# SCH_SYNTH_2024-10-22.net
KiCad netlist of a schematic drawn in EasyEDA
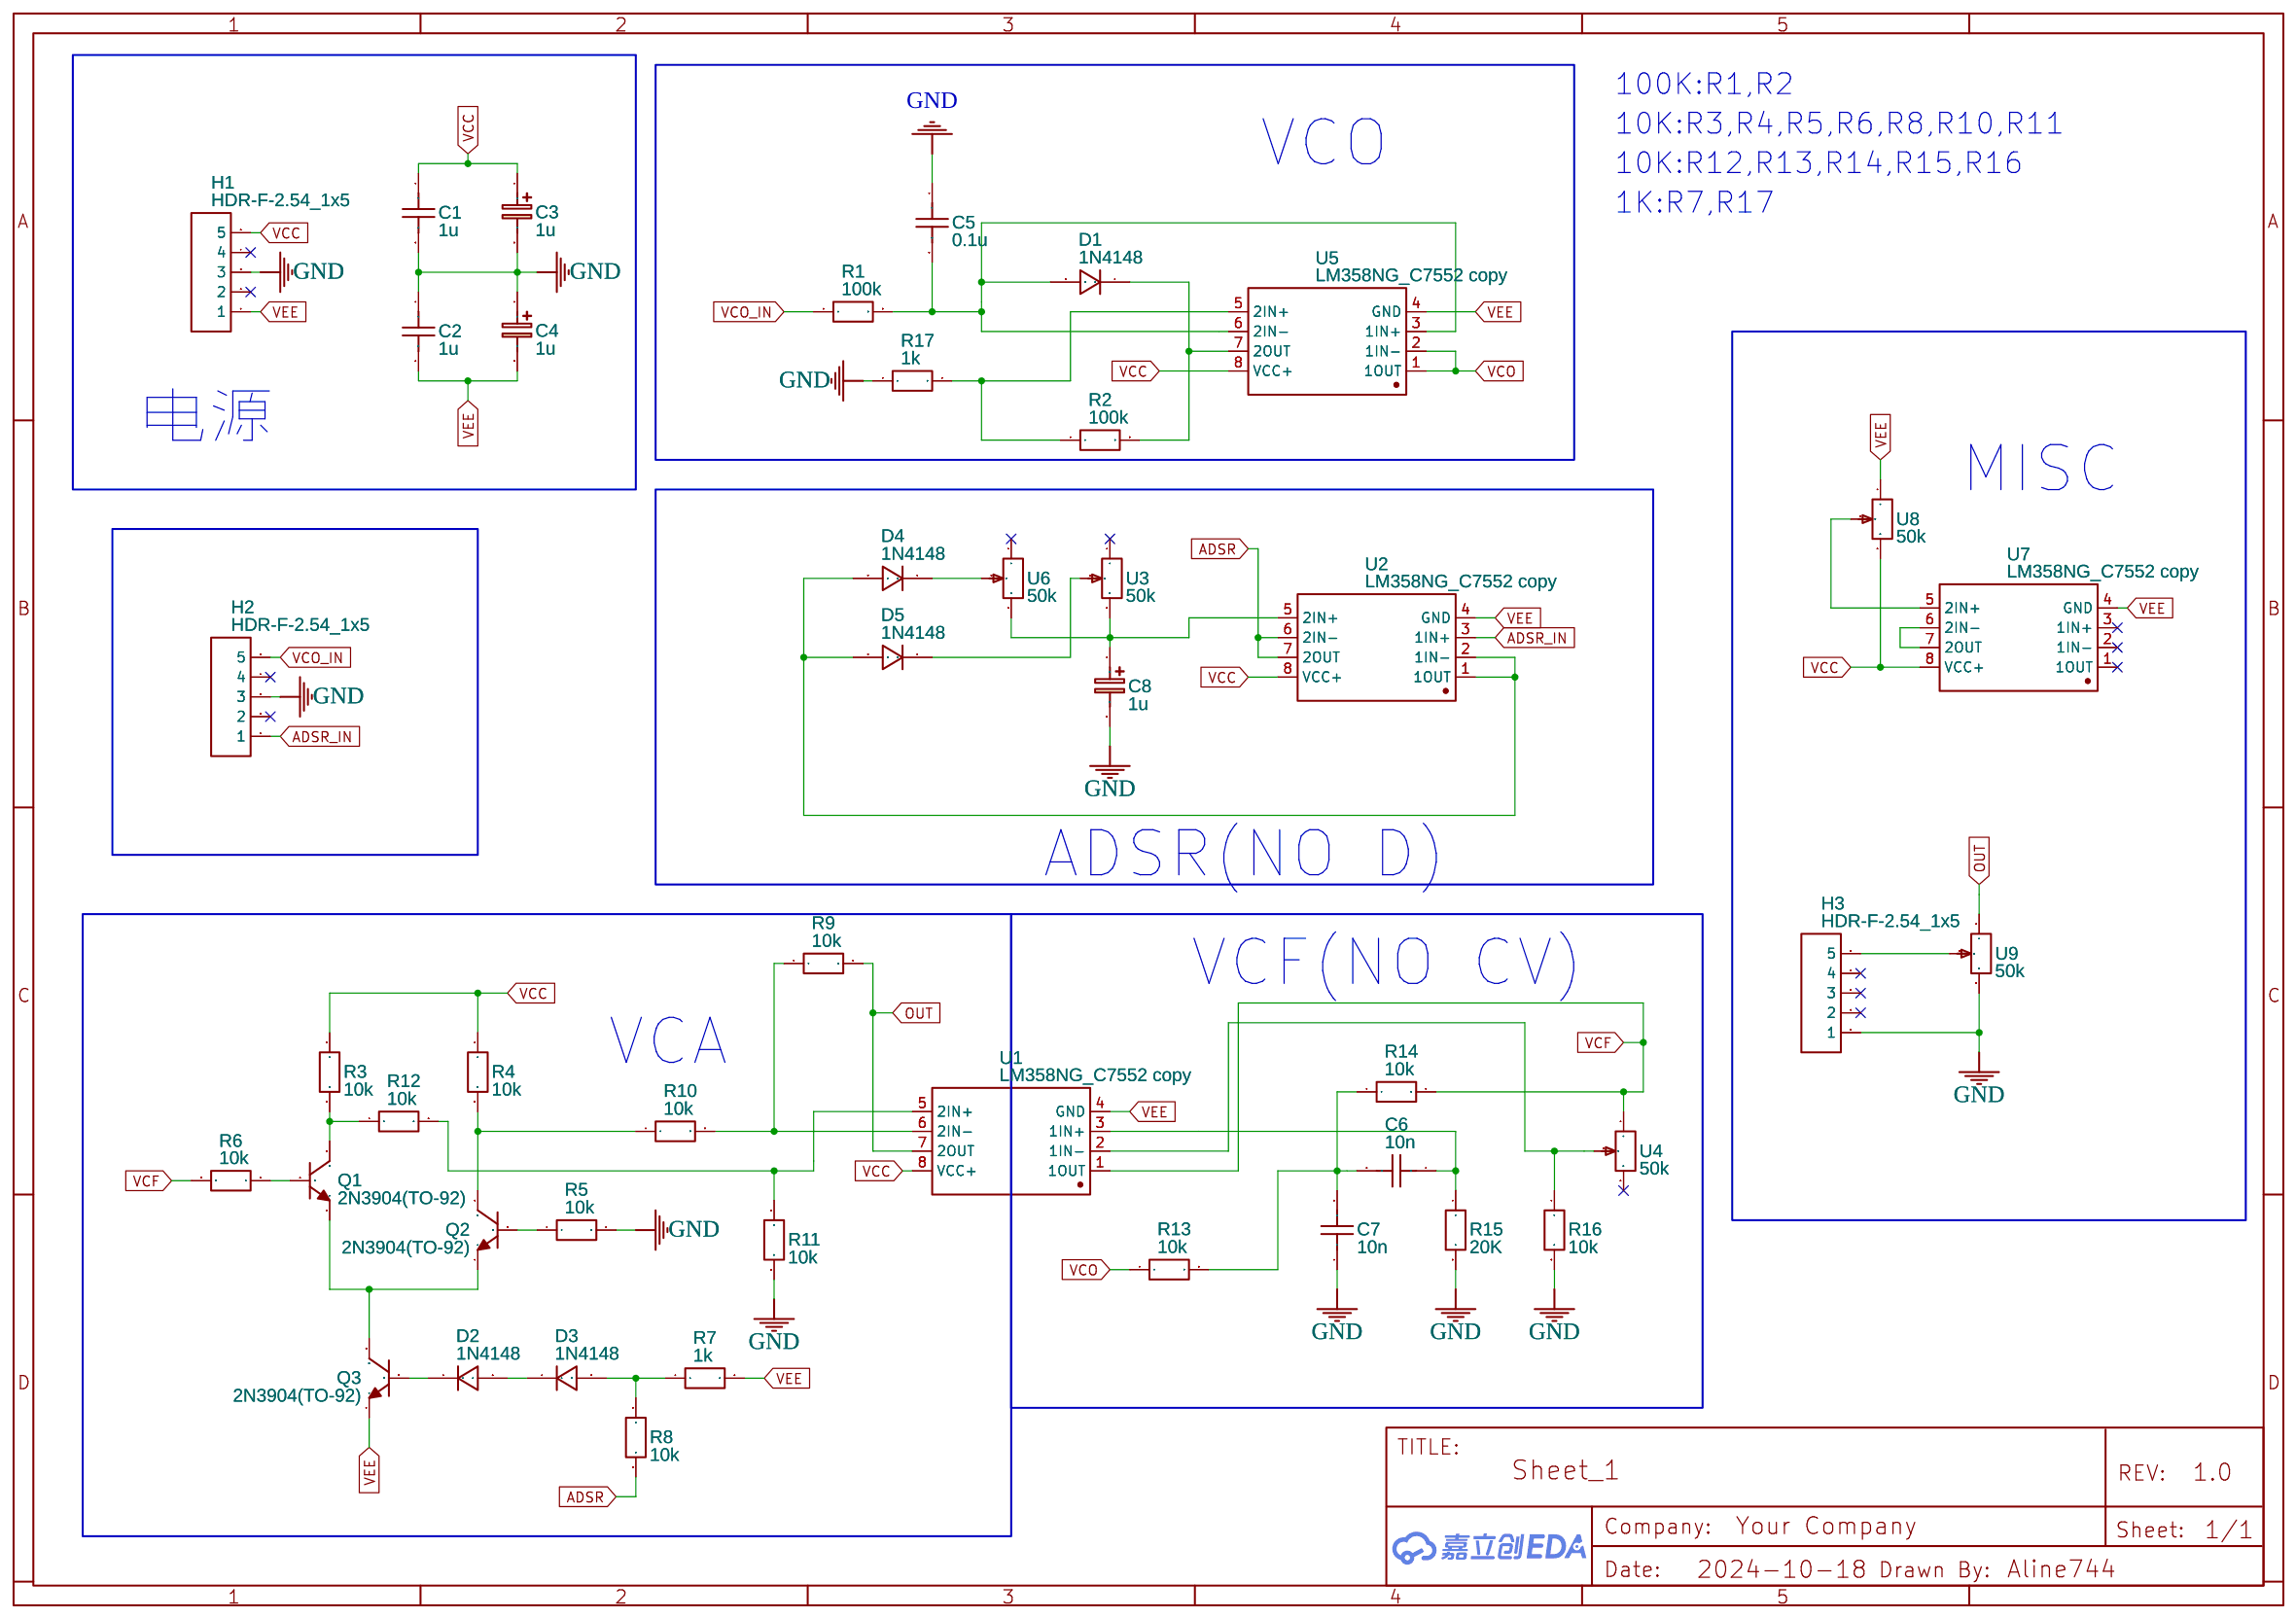
[diagram p0: schematic sheet]

(export (version "E")
  (design (tool "Eeschema 10.0.6"))
  (components
    (comp (ref "C1") (value "1u") (libsource (lib "") (part "C_RAD-0.2_US")))
    (comp (ref "C2") (value "1u") (libsource (lib "") (part "C_RAD-0.2_US")))
    (comp (ref "C3") (value "1u") (libsource (lib "") (part "CE_TH_D8.0×F3.5_EU_1")))
    (comp (ref "C4") (value "1u") (libsource (lib "") (part "CE_TH_D8.0×F3.5_EU_1")))
    (comp (ref "C5") (value "0.1u") (libsource (lib "") (part "C_RAD-0.2_US")))
    (comp (ref "C6") (value "10n") (libsource (lib "") (part "C_RAD-0.2_US_1")))
    (comp (ref "C7") (value "10n") (libsource (lib "") (part "C_RAD-0.2_US_2")))
    (comp (ref "C8") (value "1u") (libsource (lib "") (part "CE_TH_D8.0×F3.5_EU")))
    (comp (ref "D1")
      (value "1N4148")
      (fields (field (name "BOM_Supplier Part") "C13769"))
      (libsource (lib "") (part "1N4148"))
    )
    (comp (ref "D2")
      (value "1N4148")
      (fields (field (name "BOM_Supplier Part") "C13769"))
      (libsource (lib "") (part "1N4148_1"))
    )
    (comp (ref "D3")
      (value "1N4148")
      (fields (field (name "BOM_Supplier Part") "C13769"))
      (libsource (lib "") (part "1N4148_1"))
    )
    (comp (ref "D4")
      (value "1N4148")
      (fields (field (name "BOM_Supplier Part") "C13769"))
      (libsource (lib "") (part "1N4148"))
    )
    (comp (ref "D5")
      (value "1N4148")
      (fields (field (name "BOM_Supplier Part") "C13769"))
      (libsource (lib "") (part "1N4148"))
    )
    (comp (ref "H1")
      (value "HDR-F-2.54_1x5")
      (fields (field (name "BOM_Supplier Part") "C50950"))
      (libsource (lib "") (part "HDR-F-2.54_1x5"))
    )
    (comp (ref "H2")
      (value "HDR-F-2.54_1x5")
      (fields (field (name "BOM_Supplier Part") "C50950"))
      (libsource (lib "") (part "HDR-F-2.54_1x5"))
    )
    (comp (ref "H3")
      (value "HDR-F-2.54_1x5")
      (fields (field (name "BOM_Supplier Part") "C50950"))
      (libsource (lib "") (part "HDR-F-2.54_1x5"))
    )
    (comp (ref "Q1")
      (value "2N3904(TO-92)")
      (fields (field (name "BOM_Manufacturer Part") "2N3904") (field (name "BOM_Supplier Part") "C118538"))
      (libsource (lib "") (part "2N3904(TO-92)"))
    )
    (comp (ref "Q2")
      (value "2N3904(TO-92)")
      (fields (field (name "BOM_Manufacturer Part") "2N3904") (field (name "BOM_Supplier Part") "C118538"))
      (libsource (lib "") (part "2N3904(TO-92)_1"))
    )
    (comp (ref "Q3")
      (value "2N3904(TO-92)")
      (fields (field (name "BOM_Manufacturer Part") "2N3904") (field (name "BOM_Supplier Part") "C118538"))
      (libsource (lib "") (part "2N3904(TO-92)_1"))
    )
    (comp (ref "R1") (value "100k") (libsource (lib "") (part "R_AXIAL-0.3_EU_1")))
    (comp (ref "R2") (value "100k") (libsource (lib "") (part "R_AXIAL-0.3_EU_1")))
    (comp (ref "R3") (value "10k") (libsource (lib "") (part "R_AXIAL-0.3_EU")))
    (comp (ref "R4") (value "10k") (libsource (lib "") (part "R_AXIAL-0.3_EU")))
    (comp (ref "R5") (value "10k") (libsource (lib "") (part "R_AXIAL-0.3_EU_1")))
    (comp (ref "R6") (value "10k") (libsource (lib "") (part "R_AXIAL-0.3_EU_2")))
    (comp (ref "R7") (value "1k") (libsource (lib "") (part "R_AXIAL-0.3_EU_1")))
    (comp (ref "R8") (value "10k") (libsource (lib "") (part "R_AXIAL-0.3_EU")))
    (comp (ref "R9") (value "10k") (libsource (lib "") (part "R_AXIAL-0.3_EU_1")))
    (comp (ref "R10") (value "10k") (libsource (lib "") (part "R_AXIAL-0.3_EU_1")))
    (comp (ref "R11") (value "10k") (libsource (lib "") (part "R_AXIAL-0.3_EU")))
    (comp (ref "R12") (value "10k") (libsource (lib "") (part "R_AXIAL-0.3_EU_1")))
    (comp (ref "R13") (value "10k") (libsource (lib "") (part "R_AXIAL-0.3_EU_1")))
    (comp (ref "R14") (value "10k") (libsource (lib "") (part "R_AXIAL-0.3_EU_1")))
    (comp (ref "R15") (value "20K") (libsource (lib "") (part "R_AXIAL-0.3_EU")))
    (comp (ref "R16") (value "10k") (libsource (lib "") (part "R_AXIAL-0.3_EU")))
    (comp (ref "R17") (value "1k") (libsource (lib "") (part "R_AXIAL-0.3_EU_1")))
    (comp (ref "U1")
      (value "LM358NG_C7552 copy")
      (fields (field (name "Manufacturer Part") "LM358NG") (field (name "Manufacturer") "ON"))
      (libsource (lib "") (part "LM358NG_C7552 copy"))
    )
    (comp (ref "U2")
      (value "LM358NG_C7552 copy")
      (fields (field (name "Manufacturer Part") "LM358NG") (field (name "Manufacturer") "ON"))
      (libsource (lib "") (part "LM358NG_C7552 copy"))
    )
    (comp (ref "U3") (value "50k") (libsource (lib "") (part "蓝白可调电阻")))
    (comp (ref "U4") (value "50k") (libsource (lib "") (part "蓝白可调电阻")))
    (comp (ref "U5")
      (value "LM358NG_C7552 copy")
      (fields (field (name "Manufacturer Part") "LM358NG") (field (name "Manufacturer") "ON"))
      (libsource (lib "") (part "LM358NG_C7552 copy"))
    )
    (comp (ref "U6") (value "50k") (libsource (lib "") (part "蓝白可调电阻")))
    (comp (ref "U7")
      (value "LM358NG_C7552 copy")
      (fields (field (name "Manufacturer Part") "LM358NG") (field (name "Manufacturer") "ON"))
      (libsource (lib "") (part "LM358NG_C7552 copy"))
    )
    (comp (ref "U8") (value "50k") (libsource (lib "") (part "蓝白可调电阻")))
    (comp (ref "U9") (value "50k") (libsource (lib "") (part "蓝白可调电阻")))
  )
  (nets
    (net (code "1") (name "ADSR") (class "Default")
      (node (ref "R8") (pin "2") (pinfunction "2_2") (pintype "unspecified"))
      (node (ref "U2") (pin "6") (pinfunction "2IN-_6") (pintype "unspecified"))
      (node (ref "U2") (pin "7") (pinfunction "2OUT_7") (pintype "unspecified"))
    )
    (net (code "2") (name "ADSR_IN") (class "Default")
      (node (ref "H2") (pin "1") (pinfunction "1_1") (pintype "unspecified"))
      (node (ref "U2") (pin "3") (pinfunction "1IN+_3") (pintype "unspecified"))
    )
    (net (code "3") (name "GND") (class "Default")
      (node (ref "C1") (pin "2") (pinfunction "2_2") (pintype "unspecified"))
      (node (ref "C2") (pin "1") (pinfunction "1_1") (pintype "unspecified"))
      (node (ref "C3") (pin "2") (pinfunction "2_2") (pintype "unspecified"))
      (node (ref "C4") (pin "1") (pinfunction "1_1") (pintype "unspecified"))
      (node (ref "C5") (pin "1") (pinfunction "1_1") (pintype "unspecified"))
      (node (ref "C7") (pin "1") (pinfunction "1_1") (pintype "unspecified"))
      (node (ref "C8") (pin "2") (pinfunction "2_2") (pintype "unspecified"))
      (node (ref "H1") (pin "3") (pinfunction "3_3") (pintype "unspecified"))
      (node (ref "H2") (pin "3") (pinfunction "3_3") (pintype "unspecified"))
      (node (ref "H3") (pin "1") (pinfunction "1_1") (pintype "unspecified"))
      (node (ref "R11") (pin "2") (pinfunction "2_2") (pintype "unspecified"))
      (node (ref "R15") (pin "2") (pinfunction "2_2") (pintype "unspecified"))
      (node (ref "R16") (pin "2") (pinfunction "2_2") (pintype "unspecified"))
      (node (ref "R17") (pin "1") (pinfunction "1_1") (pintype "unspecified"))
      (node (ref "R5") (pin "2") (pinfunction "2_2") (pintype "unspecified"))
      (node (ref "U9") (pin "2") (pinfunction "2_2") (pintype "input"))
    )
    (net (code "4") (name "Net-(C6-Pad2)") (class "Default")
      (node (ref "C6") (pin "2") (pinfunction "2_2") (pintype "unspecified"))
      (node (ref "C7") (pin "2") (pinfunction "2_2") (pintype "unspecified"))
      (node (ref "R13") (pin "2") (pinfunction "2_2") (pintype "unspecified"))
      (node (ref "R14") (pin "1") (pinfunction "1_1") (pintype "unspecified"))
    )
    (net (code "5") (name "Net-(D2-Pad2)") (class "Default")
      (node (ref "D2") (pin "2") (pinfunction "2_2") (pintype "unspecified"))
      (node (ref "D3") (pin "1") (pinfunction "1_1") (pintype "unspecified"))
    )
    (net (code "6") (name "Net-(D3-Pad2)") (class "Default")
      (node (ref "D3") (pin "2") (pinfunction "2_2") (pintype "unspecified"))
      (node (ref "R7") (pin "1") (pinfunction "1_1") (pintype "unspecified"))
      (node (ref "R8") (pin "1") (pinfunction "1_1") (pintype "unspecified"))
    )
    (net (code "7") (name "Net-(D4-Pad1)") (class "Default")
      (node (ref "D4") (pin "1") (pinfunction "1_1") (pintype "unspecified"))
      (node (ref "U6") (pin "3") (pinfunction "3_3") (pintype "input"))
    )
    (net (code "8") (name "Net-(D5-Pad1)") (class "Default")
      (node (ref "D5") (pin "1") (pinfunction "1_1") (pintype "unspecified"))
      (node (ref "U3") (pin "3") (pinfunction "3_3") (pintype "input"))
    )
    (net (code "9") (name "Net-(H3-Pad5)") (class "Default")
      (node (ref "H3") (pin "5") (pinfunction "5_5") (pintype "unspecified"))
      (node (ref "U9") (pin "3") (pinfunction "3_3") (pintype "input"))
    )
    (net (code "10") (name "Net-(Q1-B)") (class "Default")
      (node (ref "Q1") (pin "2") (pinfunction "B_2") (pintype "unspecified"))
      (node (ref "R6") (pin "1") (pinfunction "1_1") (pintype "unspecified"))
    )
    (net (code "11") (name "Net-(Q1-C)") (class "Default")
      (node (ref "Q1") (pin "3") (pinfunction "C_3") (pintype "unspecified"))
      (node (ref "R12") (pin "1") (pinfunction "1_1") (pintype "unspecified"))
      (node (ref "R3") (pin "2") (pinfunction "2_2") (pintype "unspecified"))
    )
    (net (code "12") (name "Net-(Q1-E)") (class "Default")
      (node (ref "Q1") (pin "1") (pinfunction "E_1") (pintype "unspecified"))
      (node (ref "Q2") (pin "1") (pinfunction "E_1") (pintype "unspecified"))
      (node (ref "Q3") (pin "3") (pinfunction "C_3") (pintype "unspecified"))
    )
    (net (code "13") (name "Net-(Q2-B)") (class "Default")
      (node (ref "Q2") (pin "2") (pinfunction "B_2") (pintype "unspecified"))
      (node (ref "R5") (pin "1") (pinfunction "1_1") (pintype "unspecified"))
    )
    (net (code "14") (name "Net-(Q2-C)") (class "Default")
      (node (ref "Q2") (pin "3") (pinfunction "C_3") (pintype "unspecified"))
      (node (ref "R10") (pin "1") (pinfunction "1_1") (pintype "unspecified"))
      (node (ref "R4") (pin "2") (pinfunction "2_2") (pintype "unspecified"))
    )
    (net (code "15") (name "Net-(Q3-B)") (class "Default")
      (node (ref "D2") (pin "1") (pinfunction "1_1") (pintype "unspecified"))
      (node (ref "Q3") (pin "2") (pinfunction "B_2") (pintype "unspecified"))
    )
    (net (code "16") (name "Net-(U1-1IN+)") (class "Default")
      (node (ref "C6") (pin "1") (pinfunction "1_1") (pintype "unspecified"))
      (node (ref "R15") (pin "1") (pinfunction "1_1") (pintype "unspecified"))
      (node (ref "U1") (pin "3") (pinfunction "1IN+_3") (pintype "unspecified"))
    )
    (net (code "17") (name "Net-(U1-1IN-)") (class "Default")
      (node (ref "R16") (pin "1") (pinfunction "1_1") (pintype "unspecified"))
      (node (ref "U1") (pin "2") (pinfunction "1IN-_2") (pintype "unspecified"))
      (node (ref "U4") (pin "3") (pinfunction "3_3") (pintype "input"))
    )
    (net (code "18") (name "Net-(U1-2IN+)") (class "Default")
      (node (ref "R11") (pin "1") (pinfunction "1_1") (pintype "unspecified"))
      (node (ref "R12") (pin "2") (pinfunction "2_2") (pintype "unspecified"))
      (node (ref "U1") (pin "5") (pinfunction "2IN+_5") (pintype "unspecified"))
    )
    (net (code "19") (name "Net-(U1-2IN-)") (class "Default")
      (node (ref "R10") (pin "2") (pinfunction "2_2") (pintype "unspecified"))
      (node (ref "R9") (pin "1") (pinfunction "1_1") (pintype "unspecified"))
      (node (ref "U1") (pin "6") (pinfunction "2IN-_6") (pintype "unspecified"))
    )
    (net (code "20") (name "Net-(U2-1IN-)") (class "Default")
      (node (ref "D4") (pin "2") (pinfunction "2_2") (pintype "unspecified"))
      (node (ref "D5") (pin "2") (pinfunction "2_2") (pintype "unspecified"))
      (node (ref "U2") (pin "1") (pinfunction "1OUT_1") (pintype "unspecified"))
      (node (ref "U2") (pin "2") (pinfunction "1IN-_2") (pintype "unspecified"))
    )
    (net (code "21") (name "Net-(U2-2IN+)") (class "Default")
      (node (ref "C8") (pin "1") (pinfunction "1_1") (pintype "unspecified"))
      (node (ref "U2") (pin "5") (pinfunction "2IN+_5") (pintype "unspecified"))
      (node (ref "U3") (pin "2") (pinfunction "2_2") (pintype "input"))
      (node (ref "U6") (pin "2") (pinfunction "2_2") (pintype "input"))
    )
    (net (code "22") (name "Net-(U5-1IN+)") (class "Default")
      (node (ref "C5") (pin "2") (pinfunction "2_2") (pintype "unspecified"))
      (node (ref "D1") (pin "2") (pinfunction "2_2") (pintype "unspecified"))
      (node (ref "R1") (pin "2") (pinfunction "2_2") (pintype "unspecified"))
      (node (ref "U5") (pin "3") (pinfunction "1IN+_3") (pintype "unspecified"))
      (node (ref "U5") (pin "6") (pinfunction "2IN-_6") (pintype "unspecified"))
    )
    (net (code "23") (name "Net-(U5-2IN+)") (class "Default")
      (node (ref "R17") (pin "2") (pinfunction "2_2") (pintype "unspecified"))
      (node (ref "R2") (pin "1") (pinfunction "1_1") (pintype "unspecified"))
      (node (ref "U5") (pin "5") (pinfunction "2IN+_5") (pintype "unspecified"))
    )
    (net (code "24") (name "Net-(U5-2OUT)") (class "Default")
      (node (ref "D1") (pin "1") (pinfunction "1_1") (pintype "unspecified"))
      (node (ref "R2") (pin "2") (pinfunction "2_2") (pintype "unspecified"))
      (node (ref "U5") (pin "7") (pinfunction "2OUT_7") (pintype "unspecified"))
    )
    (net (code "25") (name "Net-(U7-2IN+)") (class "Default")
      (node (ref "U7") (pin "5") (pinfunction "2IN+_5") (pintype "unspecified"))
      (node (ref "U8") (pin "3") (pinfunction "3_3") (pintype "input"))
    )
    (net (code "26") (name "Net-(U7-2IN-)") (class "Default")
      (node (ref "U7") (pin "6") (pinfunction "2IN-_6") (pintype "unspecified"))
      (node (ref "U7") (pin "7") (pinfunction "2OUT_7") (pintype "unspecified"))
    )
    (net (code "27") (name "OUT") (class "Default")
      (node (ref "R9") (pin "2") (pinfunction "2_2") (pintype "unspecified"))
      (node (ref "U1") (pin "7") (pinfunction "2OUT_7") (pintype "unspecified"))
      (node (ref "U9") (pin "1") (pinfunction "1_1") (pintype "input"))
    )
    (net (code "28") (name "VCC") (class "Default")
      (node (ref "C1") (pin "1") (pinfunction "1_1") (pintype "unspecified"))
      (node (ref "C3") (pin "1") (pinfunction "1_1") (pintype "unspecified"))
      (node (ref "H1") (pin "5") (pinfunction "5_5") (pintype "unspecified"))
      (node (ref "R3") (pin "1") (pinfunction "1_1") (pintype "unspecified"))
      (node (ref "R4") (pin "1") (pinfunction "1_1") (pintype "unspecified"))
      (node (ref "U1") (pin "8") (pinfunction "VCC+_8") (pintype "unspecified"))
      (node (ref "U2") (pin "8") (pinfunction "VCC+_8") (pintype "unspecified"))
      (node (ref "U5") (pin "8") (pinfunction "VCC+_8") (pintype "unspecified"))
      (node (ref "U7") (pin "8") (pinfunction "VCC+_8") (pintype "unspecified"))
      (node (ref "U8") (pin "2") (pinfunction "2_2") (pintype "input"))
    )
    (net (code "29") (name "VCF") (class "Default")
      (node (ref "R14") (pin "2") (pinfunction "2_2") (pintype "unspecified"))
      (node (ref "R6") (pin "2") (pinfunction "2_2") (pintype "unspecified"))
      (node (ref "U1") (pin "1") (pinfunction "1OUT_1") (pintype "unspecified"))
      (node (ref "U4") (pin "1") (pinfunction "1_1") (pintype "input"))
    )
    (net (code "30") (name "VCO") (class "Default")
      (node (ref "R13") (pin "1") (pinfunction "1_1") (pintype "unspecified"))
      (node (ref "U5") (pin "1") (pinfunction "1OUT_1") (pintype "unspecified"))
      (node (ref "U5") (pin "2") (pinfunction "1IN-_2") (pintype "unspecified"))
    )
    (net (code "31") (name "VCO_IN") (class "Default")
      (node (ref "H2") (pin "5") (pinfunction "5_5") (pintype "unspecified"))
      (node (ref "R1") (pin "1") (pinfunction "1_1") (pintype "unspecified"))
    )
    (net (code "32") (name "VEE") (class "Default")
      (node (ref "C2") (pin "2") (pinfunction "2_2") (pintype "unspecified"))
      (node (ref "C4") (pin "2") (pinfunction "2_2") (pintype "unspecified"))
      (node (ref "H1") (pin "1") (pinfunction "1_1") (pintype "unspecified"))
      (node (ref "Q3") (pin "1") (pinfunction "E_1") (pintype "unspecified"))
      (node (ref "R7") (pin "2") (pinfunction "2_2") (pintype "unspecified"))
      (node (ref "U1") (pin "4") (pinfunction "GND_4") (pintype "unspecified"))
      (node (ref "U2") (pin "4") (pinfunction "GND_4") (pintype "unspecified"))
      (node (ref "U5") (pin "4") (pinfunction "GND_4") (pintype "unspecified"))
      (node (ref "U7") (pin "4") (pinfunction "GND_4") (pintype "unspecified"))
      (node (ref "U8") (pin "1") (pinfunction "1_1") (pintype "input"))
    )
    (net (code "33") (name "unconnected-(H1-Pad2)") (class "Default")
      (node (ref "H1") (pin "2") (pinfunction "2_2") (pintype "unspecified+no_connect"))
    )
    (net (code "34") (name "unconnected-(H1-Pad4)") (class "Default")
      (node (ref "H1") (pin "4") (pinfunction "4_4") (pintype "unspecified+no_connect"))
    )
    (net (code "35") (name "unconnected-(H2-Pad2)") (class "Default")
      (node (ref "H2") (pin "2") (pinfunction "2_2") (pintype "unspecified+no_connect"))
    )
    (net (code "36") (name "unconnected-(H2-Pad4)") (class "Default")
      (node (ref "H2") (pin "4") (pinfunction "4_4") (pintype "unspecified+no_connect"))
    )
    (net (code "37") (name "unconnected-(H3-Pad2)") (class "Default")
      (node (ref "H3") (pin "2") (pinfunction "2_2") (pintype "unspecified+no_connect"))
    )
    (net (code "38") (name "unconnected-(H3-Pad3)") (class "Default")
      (node (ref "H3") (pin "3") (pinfunction "3_3") (pintype "unspecified+no_connect"))
    )
    (net (code "39") (name "unconnected-(H3-Pad4)") (class "Default")
      (node (ref "H3") (pin "4") (pinfunction "4_4") (pintype "unspecified+no_connect"))
    )
    (net (code "40") (name "unconnected-(U3-Pad1)") (class "Default")
      (node (ref "U3") (pin "1") (pinfunction "1_1") (pintype "input+no_connect"))
    )
    (net (code "41") (name "unconnected-(U4-Pad2)") (class "Default")
      (node (ref "U4") (pin "2") (pinfunction "2_2") (pintype "input+no_connect"))
    )
    (net (code "42") (name "unconnected-(U6-Pad1)") (class "Default")
      (node (ref "U6") (pin "1") (pinfunction "1_1") (pintype "input+no_connect"))
    )
    (net (code "43") (name "unconnected-(U7-1IN+-Pad3)") (class "Default")
      (node (ref "U7") (pin "3") (pinfunction "1IN+_3") (pintype "unspecified+no_connect"))
    )
    (net (code "44") (name "unconnected-(U7-1IN--Pad2)") (class "Default")
      (node (ref "U7") (pin "2") (pinfunction "1IN-_2") (pintype "unspecified+no_connect"))
    )
    (net (code "45") (name "unconnected-(U7-1OUT-Pad1)") (class "Default")
      (node (ref "U7") (pin "1") (pinfunction "1OUT_1") (pintype "unspecified+no_connect"))
    )
  )
)
